# ACS_5_X_Breadboard_Prototype.net
KiCad netlist of a schematic drawn in EAGLE
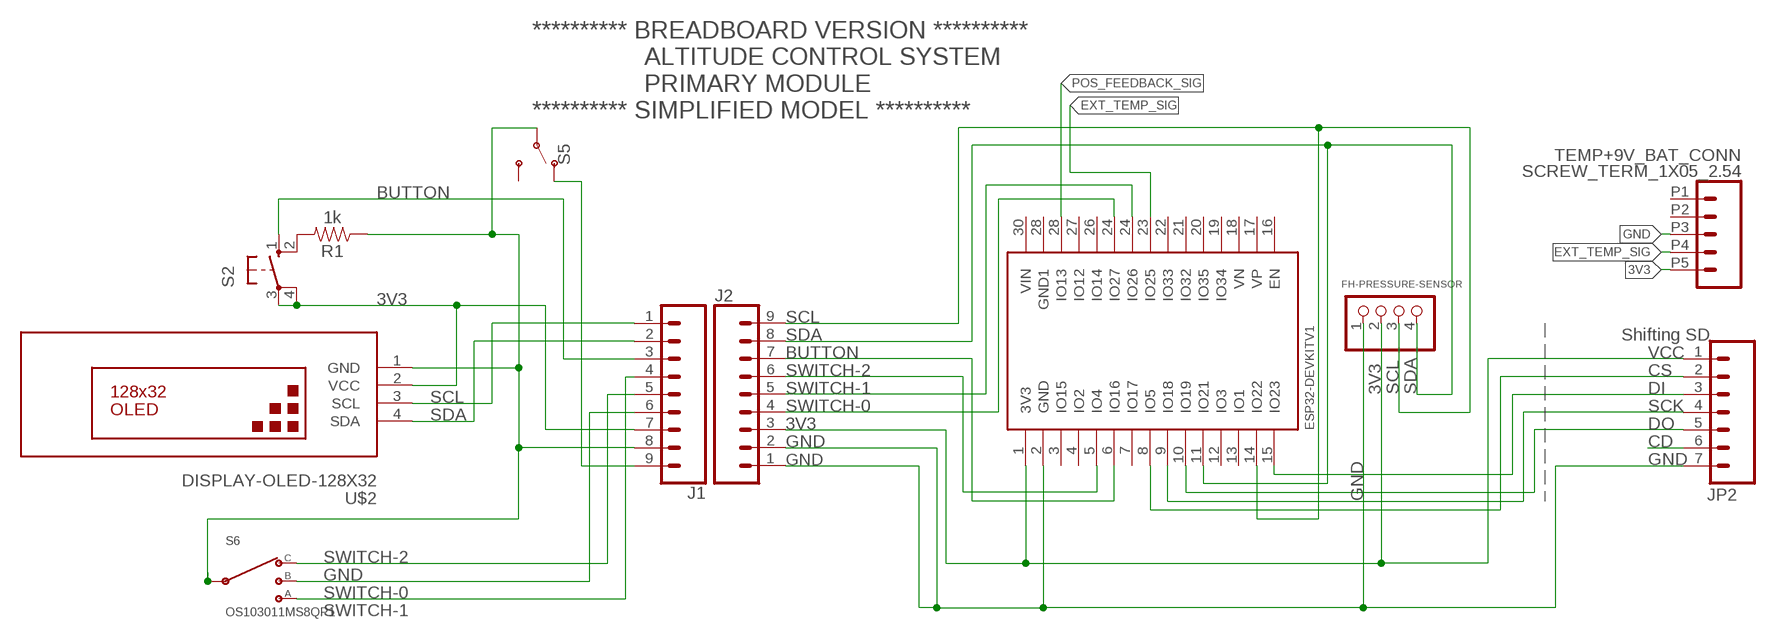
[diagram p0: schematic, sheet 1]

(export (version "E")
  (design (tool "Eeschema 10.0.6"))
  (components
    (comp (ref "FH-PRESSURE-SENSOR")
      (value "PINHD-1X4")
      (footprint "eagle-import:1X04")
      (libsource (lib "eagle-import") (part "PINHD-1X4"))
    )
    (comp (ref "J1")
      (value "CONN_09")
      (footprint "eagle-import:1X09")
      (libsource (lib "eagle-import") (part "CONN_09"))
    )
    (comp (ref "J2")
      (value "CONN_09")
      (footprint "eagle-import:1X09")
      (libsource (lib "eagle-import") (part "CONN_09"))
    )
    (comp (ref "JP2")
      (value "M07")
      (footprint "eagle-import:1X07")
      (libsource (lib "eagle-import") (part "M07"))
    )
    (comp (ref "R1")
      (value "1k")
      (footprint "eagle-import:AXIAL-0.3")
      (libsource (lib "eagle-import") (part "1KOHM-HORIZ-1/4W-1%"))
    )
    (comp (ref "S2")
      (value "10-XX")
      (footprint "eagle-import:B3F-10XX")
      (fields (field (name "MPN") "B3F-1000"))
      (libsource (lib "eagle-import") (part "10-XX"))
    )
    (comp (ref "S5")
      (value "SWITCH-SPDT-PTH-11.6X4.0MM")
      (footprint "eagle-import:SWITCH_SPDT_PTH_11.6X4.0MM")
      (libsource (lib "eagle-import") (part "SWITCH-SPDT-PTH-11.6X4.0MM"))
    )
    (comp (ref "S6")
      (value "OS103011MS8QP1")
      (footprint "eagle-import:OS102011MS8QP1")
      (fields (field (name "MF") "C&K"))
      (libsource (lib "eagle-import") (part "OS103011MS8QP1"))
    )
    (comp (ref "TEMP+9V_BAT_CONN")
      (value "SCREW_TERM_1X05_2.54")
      (footprint "eagle-import:1X05_2.54_SCREWTERM")
      (libsource (lib "eagle-import") (part "SCREW_TERM_1X05_2.54"))
    )
    (comp (ref "U$2")
      (value "DISPLAY-OLED-128X32")
      (footprint "eagle-import:DISPLAY-OLED-128X32")
      (libsource (lib "eagle-import") (part "DISPLAY-OLED-128X32"))
    )
    (comp (ref "U$3")
      (value "ESP32DEVKITV1")
      (footprint "eagle-import:ESP32-DEVKITV1")
      (libsource (lib "eagle-import") (part "ESP32DEVKITV1"))
    )
  )
  (nets
    (net (code "1") (name "/BUTTON") (class "Default")
      (node (ref "J1") (pin "3") (pinfunction "3_3") (pintype "passive"))
      (node (ref "J2") (pin "7") (pinfunction "7_7") (pintype "passive"))
      (node (ref "S2") (pin "1") (pinfunction "S_1") (pintype "passive"))
      (node (ref "U$3") (pin "6") (pinfunction "IO16_6") (pintype "bidirectional"))
    )
    (net (code "2") (name "/SCL") (class "Default")
      (node (ref "FH-PRESSURE-SENSOR") (pin "3") (pinfunction "3_3") (pintype "passive"))
      (node (ref "J1") (pin "1") (pinfunction "1_1") (pintype "passive"))
      (node (ref "J2") (pin "9") (pinfunction "9_9") (pintype "passive"))
      (node (ref "U$2") (pin "3") (pinfunction "SCL_3") (pintype "bidirectional"))
      (node (ref "U$3") (pin "14") (pinfunction "IO22_14") (pintype "bidirectional"))
    )
    (net (code "3") (name "/SDA") (class "Default")
      (node (ref "FH-PRESSURE-SENSOR") (pin "4") (pinfunction "4_4") (pintype "passive"))
      (node (ref "J1") (pin "2") (pinfunction "2_2") (pintype "passive"))
      (node (ref "J2") (pin "8") (pinfunction "8_8") (pintype "passive"))
      (node (ref "U$2") (pin "4") (pinfunction "SDA_4") (pintype "bidirectional"))
      (node (ref "U$3") (pin "11") (pinfunction "IO21_11") (pintype "bidirectional"))
    )
    (net (code "4") (name "/SWITCH-0") (class "Default")
      (node (ref "J1") (pin "6") (pinfunction "6_6") (pintype "passive"))
      (node (ref "J2") (pin "4") (pinfunction "4_4") (pintype "passive"))
      (node (ref "S6") (pin "3") (pinfunction "2_3") (pintype "bidirectional"))
      (node (ref "U$3") (pin "24") (pinfunction "IO27_24") (pintype "bidirectional"))
    )
    (net (code "5") (name "/SWITCH-1") (class "Default")
      (node (ref "J1") (pin "5") (pinfunction "5_5") (pintype "passive"))
      (node (ref "J2") (pin "5") (pinfunction "5_5") (pintype "passive"))
      (node (ref "S6") (pin "4") (pinfunction "3_4") (pintype "bidirectional"))
      (node (ref "U$3") (pin "24") (pinfunction "IO26_24") (pintype "bidirectional"))
    )
    (net (code "6") (name "/SWITCH-2") (class "Default")
      (node (ref "J1") (pin "4") (pinfunction "4_4") (pintype "passive"))
      (node (ref "J2") (pin "6") (pinfunction "6_6") (pintype "passive"))
      (node (ref "S6") (pin "1") (pinfunction "1_1") (pintype "bidirectional"))
      (node (ref "U$3") (pin "5") (pinfunction "IO4_5") (pintype "bidirectional"))
    )
    (net (code "7") (name "3V3") (class "Default")
      (node (ref "FH-PRESSURE-SENSOR") (pin "2") (pinfunction "2_2") (pintype "passive"))
      (node (ref "J1") (pin "7") (pinfunction "7_7") (pintype "passive"))
      (node (ref "J2") (pin "3") (pinfunction "3_3") (pintype "passive"))
      (node (ref "JP2") (pin "1") (pinfunction "1_1") (pintype "passive"))
      (node (ref "S2") (pin "3") (pinfunction "P_3") (pintype "passive"))
      (node (ref "S2") (pin "4") (pinfunction "P1_4") (pintype "passive"))
      (node (ref "TEMP+9V_BAT_CONN") (pin "P5") (pinfunction "5_P5") (pintype "passive"))
      (node (ref "U$2") (pin "2") (pinfunction "VCC_2") (pintype "power_in"))
      (node (ref "U$3") (pin "1") (pinfunction "3V3_1") (pintype "bidirectional"))
    )
    (net (code "8") (name "EXT_TEMP_SIG") (class "Default")
      (node (ref "TEMP+9V_BAT_CONN") (pin "P4") (pinfunction "4_P4") (pintype "passive"))
      (node (ref "U$3") (pin "23") (pinfunction "IO25_23") (pintype "bidirectional"))
    )
    (net (code "9") (name "GND") (class "Default")
      (node (ref "FH-PRESSURE-SENSOR") (pin "1") (pinfunction "1_1") (pintype "passive"))
      (node (ref "J1") (pin "8") (pinfunction "8_8") (pintype "passive"))
      (node (ref "J2") (pin "1") (pinfunction "1_1") (pintype "passive"))
      (node (ref "J2") (pin "2") (pinfunction "2_2") (pintype "passive"))
      (node (ref "JP2") (pin "7") (pinfunction "7_7") (pintype "passive"))
      (node (ref "R1") (pin "P$1") (pinfunction "1_P$1") (pintype "passive"))
      (node (ref "S5") (pin "2") (pinfunction "P_2") (pintype "passive"))
      (node (ref "S6") (pin "2") (pinfunction "C_2") (pintype "bidirectional"))
      (node (ref "TEMP+9V_BAT_CONN") (pin "P3") (pinfunction "3_P3") (pintype "passive"))
      (node (ref "U$2") (pin "1") (pinfunction "GND_1") (pintype "power_in"))
      (node (ref "U$3") (pin "2") (pinfunction "GND_2") (pintype "bidirectional"))
    )
    (net (code "10") (name "Net-(R1-2)") (class "Default")
      (node (ref "R1") (pin "P$2") (pinfunction "2_P$2") (pintype "passive"))
      (node (ref "S2") (pin "2") (pinfunction "S1_2") (pintype "passive"))
    )
    (net (code "11") (name "Net-(S5-O)") (class "Default")
      (node (ref "J1") (pin "9") (pinfunction "9_9") (pintype "passive"))
      (node (ref "S5") (pin "1") (pinfunction "O_1") (pintype "passive"))
    )
    (net (code "12") (name "Net-(U$3-IO5)") (class "Default")
      (node (ref "JP2") (pin "2") (pinfunction "2_2") (pintype "passive"))
      (node (ref "U$3") (pin "8") (pinfunction "IO5_8") (pintype "bidirectional"))
    )
    (net (code "13") (name "Net-(U$3-IO18)") (class "Default")
      (node (ref "JP2") (pin "4") (pinfunction "4_4") (pintype "passive"))
      (node (ref "U$3") (pin "9") (pinfunction "IO18_9") (pintype "bidirectional"))
    )
    (net (code "14") (name "Net-(U$3-IO19)") (class "Default")
      (node (ref "JP2") (pin "5") (pinfunction "5_5") (pintype "passive"))
      (node (ref "U$3") (pin "10") (pinfunction "IO19_10") (pintype "bidirectional"))
    )
    (net (code "15") (name "Net-(U$3-IO23)") (class "Default")
      (node (ref "JP2") (pin "3") (pinfunction "3_3") (pintype "passive"))
      (node (ref "U$3") (pin "15") (pinfunction "IO23_15") (pintype "bidirectional"))
    )
    (net (code "16") (name "POS_FEEDBACK_SIG") (class "Default")
      (node (ref "U$3") (pin "28") (pinfunction "IO13_28") (pintype "bidirectional"))
    )
    (net (code "17") (name "unconnected-(JP2-Pad6)") (class "Default")
      (node (ref "JP2") (pin "6") (pinfunction "6_6") (pintype "passive"))
    )
    (net (code "18") (name "unconnected-(S5-S-Pad3)") (class "Default")
      (node (ref "S5") (pin "3") (pinfunction "S_3") (pintype "passive"))
    )
    (net (code "19") (name "unconnected-(TEMP+9V_BAT_CONN-1-PadP1)") (class "Default")
      (node (ref "TEMP+9V_BAT_CONN") (pin "P1") (pinfunction "1_P1") (pintype "passive"))
    )
    (net (code "20") (name "unconnected-(TEMP+9V_BAT_CONN-2-PadP2)") (class "Default")
      (node (ref "TEMP+9V_BAT_CONN") (pin "P2") (pinfunction "2_P2") (pintype "passive"))
    )
    (net (code "21") (name "unconnected-(U$3-EN-Pad16)") (class "Default")
      (node (ref "U$3") (pin "16") (pinfunction "EN_16") (pintype "bidirectional"))
    )
    (net (code "22") (name "unconnected-(U$3-GND1-Pad28)") (class "Default")
      (node (ref "U$3") (pin "28") (pinfunction "GND1_28") (pintype "bidirectional"))
    )
    (net (code "23") (name "unconnected-(U$3-IO1-Pad13)") (class "Default")
      (node (ref "U$3") (pin "13") (pinfunction "IO1_13") (pintype "bidirectional"))
    )
    (net (code "24") (name "unconnected-(U$3-IO2-Pad4)") (class "Default")
      (node (ref "U$3") (pin "4") (pinfunction "IO2_4") (pintype "bidirectional"))
    )
    (net (code "25") (name "unconnected-(U$3-IO3-Pad12)") (class "Default")
      (node (ref "U$3") (pin "12") (pinfunction "IO3_12") (pintype "bidirectional"))
    )
    (net (code "26") (name "unconnected-(U$3-IO12-Pad27)") (class "Default")
      (node (ref "U$3") (pin "27") (pinfunction "IO12_27") (pintype "bidirectional"))
    )
    (net (code "27") (name "unconnected-(U$3-IO14-Pad26)") (class "Default")
      (node (ref "U$3") (pin "26") (pinfunction "IO14_26") (pintype "bidirectional"))
    )
    (net (code "28") (name "unconnected-(U$3-IO15-Pad3)") (class "Default")
      (node (ref "U$3") (pin "3") (pinfunction "IO15_3") (pintype "bidirectional"))
    )
    (net (code "29") (name "unconnected-(U$3-IO17-Pad7)") (class "Default")
      (node (ref "U$3") (pin "7") (pinfunction "IO17_7") (pintype "bidirectional"))
    )
    (net (code "30") (name "unconnected-(U$3-IO32-Pad21)") (class "Default")
      (node (ref "U$3") (pin "21") (pinfunction "IO32_21") (pintype "bidirectional"))
    )
    (net (code "31") (name "unconnected-(U$3-IO33-Pad22)") (class "Default")
      (node (ref "U$3") (pin "22") (pinfunction "IO33_22") (pintype "bidirectional"))
    )
    (net (code "32") (name "unconnected-(U$3-IO34-Pad19)") (class "Default")
      (node (ref "U$3") (pin "19") (pinfunction "IO34_19") (pintype "bidirectional"))
    )
    (net (code "33") (name "unconnected-(U$3-IO35-Pad20)") (class "Default")
      (node (ref "U$3") (pin "20") (pinfunction "IO35_20") (pintype "bidirectional"))
    )
    (net (code "34") (name "unconnected-(U$3-VIN-Pad30)") (class "Default")
      (node (ref "U$3") (pin "30") (pinfunction "VIN_30") (pintype "bidirectional"))
    )
    (net (code "35") (name "unconnected-(U$3-VN-Pad18)") (class "Default")
      (node (ref "U$3") (pin "18") (pinfunction "VN_18") (pintype "bidirectional"))
    )
    (net (code "36") (name "unconnected-(U$3-VP-Pad17)") (class "Default")
      (node (ref "U$3") (pin "17") (pinfunction "VP_17") (pintype "bidirectional"))
    )
  )
)
